# 2_waffling60-MXHS_matrix.net
KiCad netlist of a schematic drawn in Altium Designer
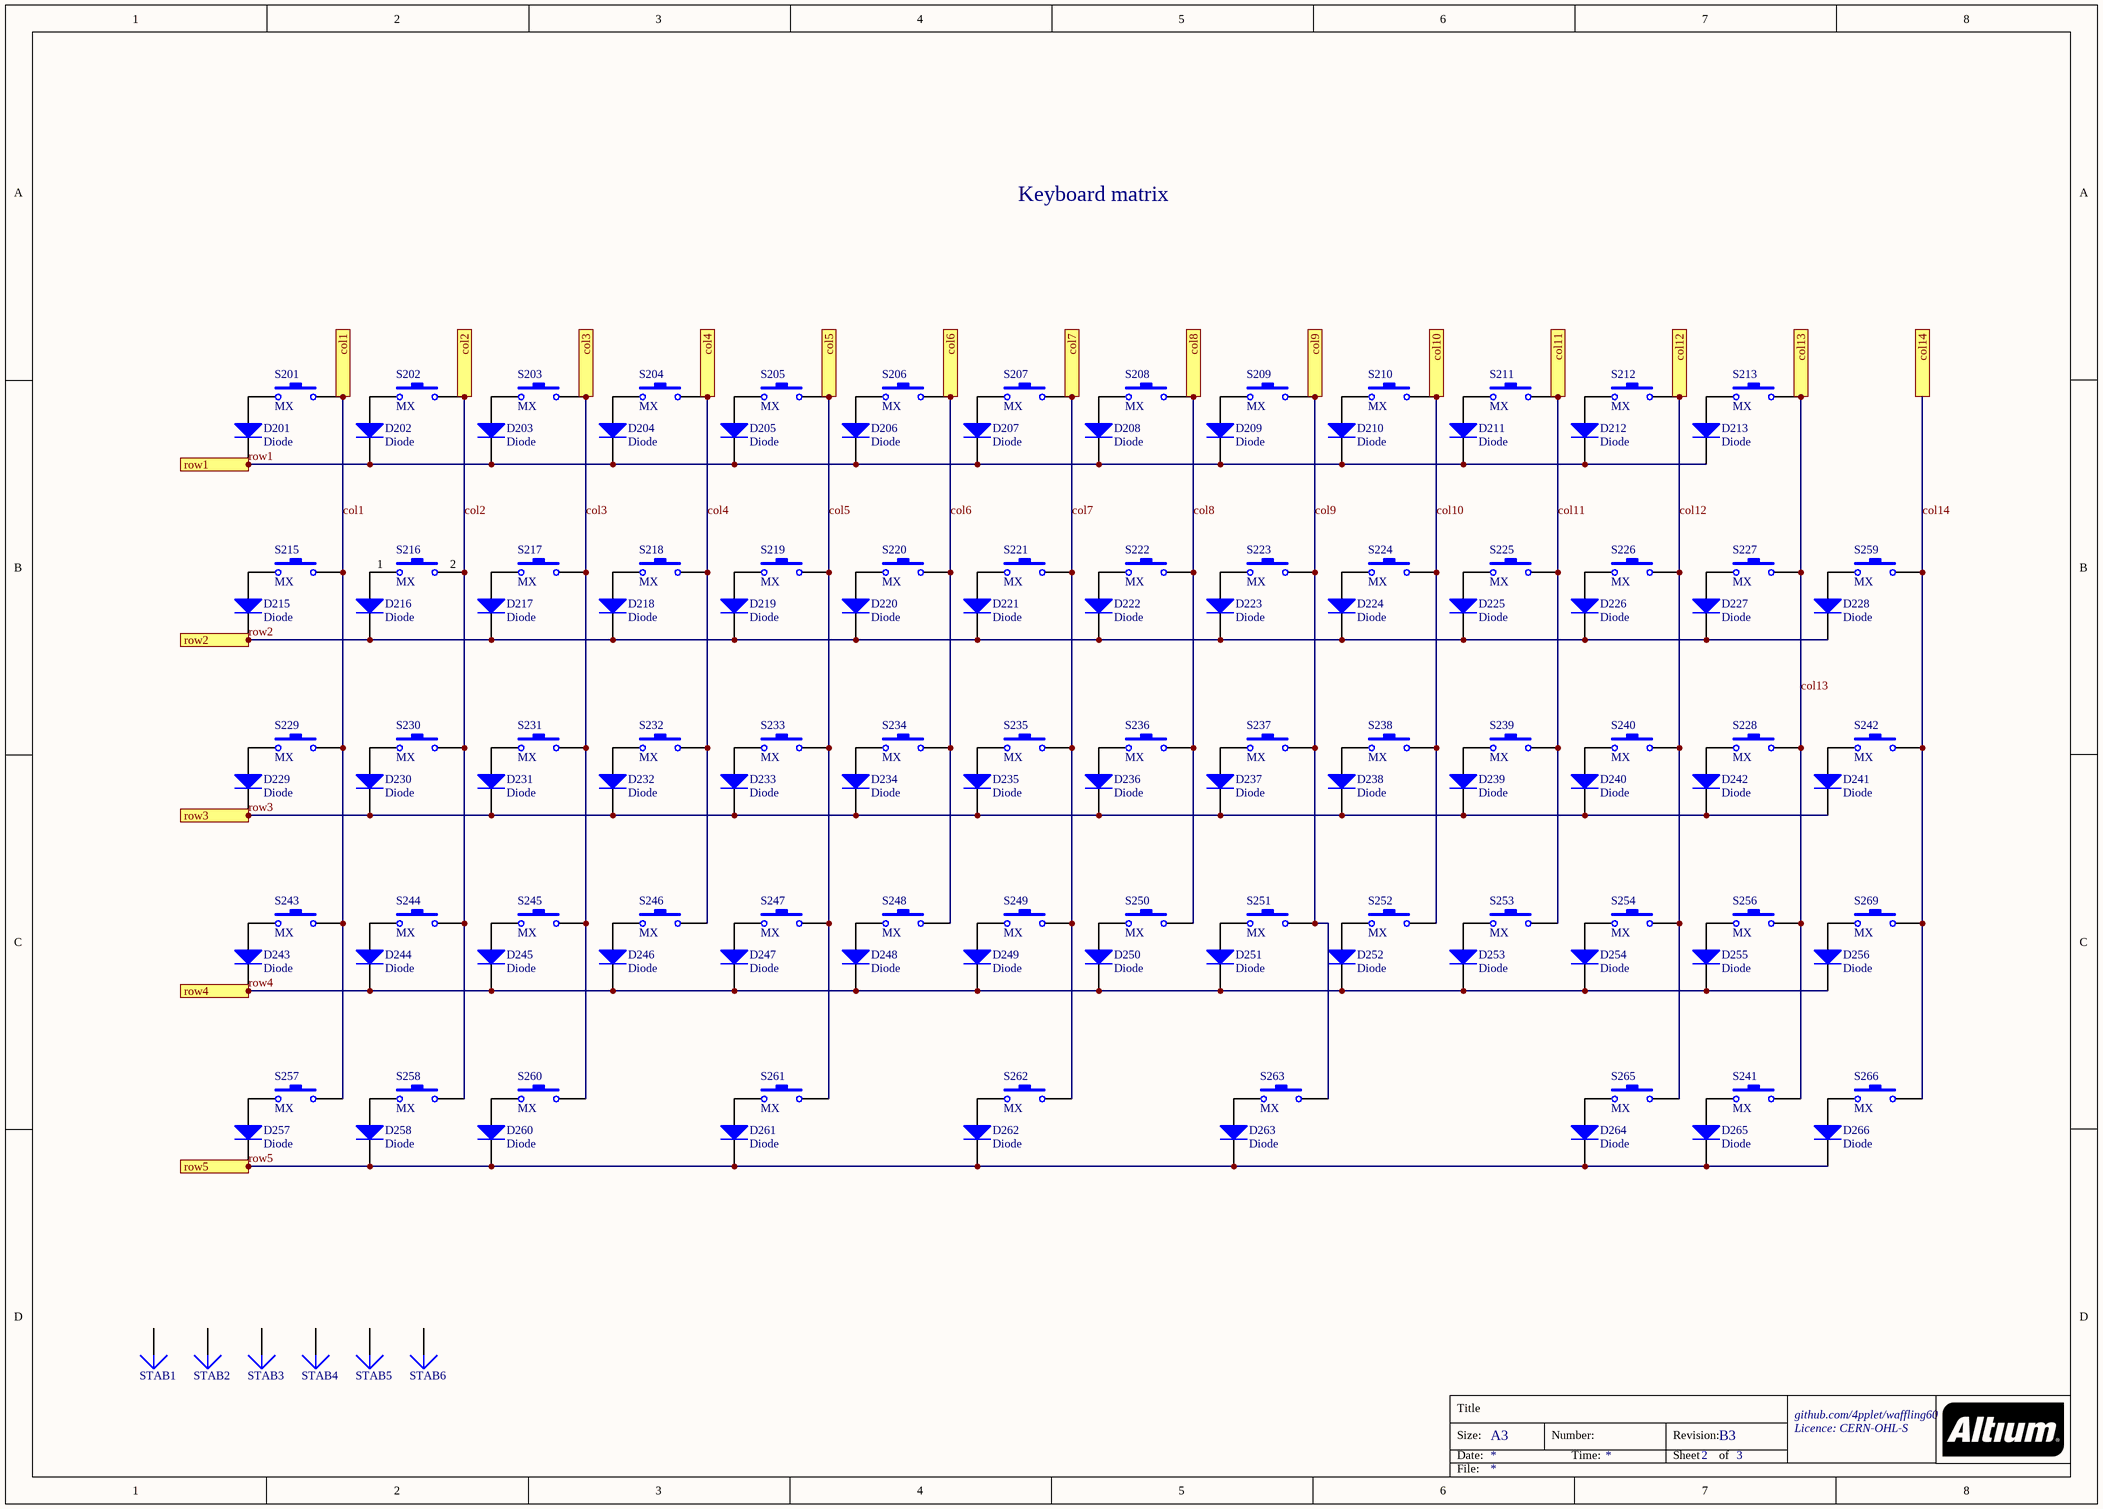
[diagram p0: 2_waffling60-MXHS_matrix.SchDoc]

(export (version "E")
  (design (tool "Eeschema 10.0.6"))
  (components
    (comp (ref "D201")
      (value "Diode")
      (footprint "SOD-123")
      (description "Default Diode")
      (fields (field (name "LCSC PART #") "C81598") (field (name "MRF.PART") "1N4148W"))
      (libsource (lib "Miscellaneous Devices") (part "Diode"))
    )
    (comp (ref "D202")
      (value "Diode")
      (footprint "SOD-123")
      (description "Default Diode")
      (fields (field (name "LCSC PART #") "C81598") (field (name "MRF.PART") "1N4148W"))
      (libsource (lib "Miscellaneous Devices") (part "Diode"))
    )
    (comp (ref "D203")
      (value "Diode")
      (footprint "SOD-123")
      (description "Default Diode")
      (fields (field (name "LCSC PART #") "C81598") (field (name "MRF.PART") "1N4148W"))
      (libsource (lib "Miscellaneous Devices") (part "Diode"))
    )
    (comp (ref "D204")
      (value "Diode")
      (footprint "SOD-123")
      (description "Default Diode")
      (fields (field (name "LCSC PART #") "C81598") (field (name "MRF.PART") "1N4148W"))
      (libsource (lib "Miscellaneous Devices") (part "Diode"))
    )
    (comp (ref "D205")
      (value "Diode")
      (footprint "SOD-123")
      (description "Default Diode")
      (fields (field (name "LCSC PART #") "C81598") (field (name "MRF.PART") "1N4148W"))
      (libsource (lib "Miscellaneous Devices") (part "Diode"))
    )
    (comp (ref "D206")
      (value "Diode")
      (footprint "SOD-123")
      (description "Default Diode")
      (fields (field (name "LCSC PART #") "C81598") (field (name "MRF.PART") "1N4148W"))
      (libsource (lib "Miscellaneous Devices") (part "Diode"))
    )
    (comp (ref "D207")
      (value "Diode")
      (footprint "SOD-123")
      (description "Default Diode")
      (fields (field (name "LCSC PART #") "C81598") (field (name "MRF.PART") "1N4148W"))
      (libsource (lib "Miscellaneous Devices") (part "Diode"))
    )
    (comp (ref "D208")
      (value "Diode")
      (footprint "SOD-123")
      (description "Default Diode")
      (fields (field (name "LCSC PART #") "C81598") (field (name "MRF.PART") "1N4148W"))
      (libsource (lib "Miscellaneous Devices") (part "Diode"))
    )
    (comp (ref "D209")
      (value "Diode")
      (footprint "SOD-123")
      (description "Default Diode")
      (fields (field (name "LCSC PART #") "C81598") (field (name "MRF.PART") "1N4148W"))
      (libsource (lib "Miscellaneous Devices") (part "Diode"))
    )
    (comp (ref "D210")
      (value "Diode")
      (footprint "SOD-123")
      (description "Default Diode")
      (fields (field (name "LCSC PART #") "C81598") (field (name "MRF.PART") "1N4148W"))
      (libsource (lib "Miscellaneous Devices") (part "Diode"))
    )
    (comp (ref "D211")
      (value "Diode")
      (footprint "SOD-123")
      (description "Default Diode")
      (fields (field (name "LCSC PART #") "C81598") (field (name "MRF.PART") "1N4148W"))
      (libsource (lib "Miscellaneous Devices") (part "Diode"))
    )
    (comp (ref "D212")
      (value "Diode")
      (footprint "SOD-123")
      (description "Default Diode")
      (fields (field (name "LCSC PART #") "C81598") (field (name "MRF.PART") "1N4148W"))
      (libsource (lib "Miscellaneous Devices") (part "Diode"))
    )
    (comp (ref "D213")
      (value "Diode")
      (footprint "SOD-123")
      (description "Default Diode")
      (fields (field (name "LCSC PART #") "C81598") (field (name "MRF.PART") "1N4148W"))
      (libsource (lib "Miscellaneous Devices") (part "Diode"))
    )
    (comp (ref "D215")
      (value "Diode")
      (footprint "SOD-123")
      (description "Default Diode")
      (fields (field (name "LCSC PART #") "C81598") (field (name "MRF.PART") "1N4148W"))
      (libsource (lib "Miscellaneous Devices") (part "Diode"))
    )
    (comp (ref "D216")
      (value "Diode")
      (footprint "SOD-123")
      (description "Default Diode")
      (fields (field (name "LCSC PART #") "C81598") (field (name "MRF.PART") "1N4148W"))
      (libsource (lib "Miscellaneous Devices") (part "Diode"))
    )
    (comp (ref "D217")
      (value "Diode")
      (footprint "SOD-123")
      (description "Default Diode")
      (fields (field (name "LCSC PART #") "C81598") (field (name "MRF.PART") "1N4148W"))
      (libsource (lib "Miscellaneous Devices") (part "Diode"))
    )
    (comp (ref "D218")
      (value "Diode")
      (footprint "SOD-123")
      (description "Default Diode")
      (fields (field (name "LCSC PART #") "C81598") (field (name "MRF.PART") "1N4148W"))
      (libsource (lib "Miscellaneous Devices") (part "Diode"))
    )
    (comp (ref "D219")
      (value "Diode")
      (footprint "SOD-123")
      (description "Default Diode")
      (fields (field (name "LCSC PART #") "C81598") (field (name "MRF.PART") "1N4148W"))
      (libsource (lib "Miscellaneous Devices") (part "Diode"))
    )
    (comp (ref "D220")
      (value "Diode")
      (footprint "SOD-123")
      (description "Default Diode")
      (fields (field (name "LCSC PART #") "C81598") (field (name "MRF.PART") "1N4148W"))
      (libsource (lib "Miscellaneous Devices") (part "Diode"))
    )
    (comp (ref "D221")
      (value "Diode")
      (footprint "SOD-123")
      (description "Default Diode")
      (fields (field (name "LCSC PART #") "C81598") (field (name "MRF.PART") "1N4148W"))
      (libsource (lib "Miscellaneous Devices") (part "Diode"))
    )
    (comp (ref "D222")
      (value "Diode")
      (footprint "SOD-123")
      (description "Default Diode")
      (fields (field (name "LCSC PART #") "C81598") (field (name "MRF.PART") "1N4148W"))
      (libsource (lib "Miscellaneous Devices") (part "Diode"))
    )
    (comp (ref "D223")
      (value "Diode")
      (footprint "SOD-123")
      (description "Default Diode")
      (fields (field (name "LCSC PART #") "C81598") (field (name "MRF.PART") "1N4148W"))
      (libsource (lib "Miscellaneous Devices") (part "Diode"))
    )
    (comp (ref "D224")
      (value "Diode")
      (footprint "SOD-123")
      (description "Default Diode")
      (fields (field (name "LCSC PART #") "C81598") (field (name "MRF.PART") "1N4148W"))
      (libsource (lib "Miscellaneous Devices") (part "Diode"))
    )
    (comp (ref "D225")
      (value "Diode")
      (footprint "SOD-123")
      (description "Default Diode")
      (fields (field (name "LCSC PART #") "C81598") (field (name "MRF.PART") "1N4148W"))
      (libsource (lib "Miscellaneous Devices") (part "Diode"))
    )
    (comp (ref "D226")
      (value "Diode")
      (footprint "SOD-123")
      (description "Default Diode")
      (fields (field (name "LCSC PART #") "C81598") (field (name "MRF.PART") "1N4148W"))
      (libsource (lib "Miscellaneous Devices") (part "Diode"))
    )
    (comp (ref "D227")
      (value "Diode")
      (footprint "SOD-123")
      (description "Default Diode")
      (fields (field (name "LCSC PART #") "C81598") (field (name "MRF.PART") "1N4148W"))
      (libsource (lib "Miscellaneous Devices") (part "Diode"))
    )
    (comp (ref "D228")
      (value "Diode")
      (footprint "SOD-123")
      (description "Default Diode")
      (fields (field (name "LCSC PART #") "C81598") (field (name "MRF.PART") "1N4148W"))
      (libsource (lib "Miscellaneous Devices") (part "Diode"))
    )
    (comp (ref "D229")
      (value "Diode")
      (footprint "SOD-123")
      (description "Default Diode")
      (fields (field (name "LCSC PART #") "C81598") (field (name "MRF.PART") "1N4148W"))
      (libsource (lib "Miscellaneous Devices") (part "Diode"))
    )
    (comp (ref "D230")
      (value "Diode")
      (footprint "SOD-123")
      (description "Default Diode")
      (fields (field (name "LCSC PART #") "C81598") (field (name "MRF.PART") "1N4148W"))
      (libsource (lib "Miscellaneous Devices") (part "Diode"))
    )
    (comp (ref "D231")
      (value "Diode")
      (footprint "SOD-123")
      (description "Default Diode")
      (fields (field (name "LCSC PART #") "C81598") (field (name "MRF.PART") "1N4148W"))
      (libsource (lib "Miscellaneous Devices") (part "Diode"))
    )
    (comp (ref "D232")
      (value "Diode")
      (footprint "SOD-123")
      (description "Default Diode")
      (fields (field (name "LCSC PART #") "C81598") (field (name "MRF.PART") "1N4148W"))
      (libsource (lib "Miscellaneous Devices") (part "Diode"))
    )
    (comp (ref "D233")
      (value "Diode")
      (footprint "SOD-123")
      (description "Default Diode")
      (fields (field (name "LCSC PART #") "C81598") (field (name "MRF.PART") "1N4148W"))
      (libsource (lib "Miscellaneous Devices") (part "Diode"))
    )
    (comp (ref "D234")
      (value "Diode")
      (footprint "SOD-123")
      (description "Default Diode")
      (fields (field (name "LCSC PART #") "C81598") (field (name "MRF.PART") "1N4148W"))
      (libsource (lib "Miscellaneous Devices") (part "Diode"))
    )
    (comp (ref "D235")
      (value "Diode")
      (footprint "SOD-123")
      (description "Default Diode")
      (fields (field (name "LCSC PART #") "C81598") (field (name "MRF.PART") "1N4148W"))
      (libsource (lib "Miscellaneous Devices") (part "Diode"))
    )
    (comp (ref "D236")
      (value "Diode")
      (footprint "SOD-123")
      (description "Default Diode")
      (fields (field (name "LCSC PART #") "C81598") (field (name "MRF.PART") "1N4148W"))
      (libsource (lib "Miscellaneous Devices") (part "Diode"))
    )
    (comp (ref "D237")
      (value "Diode")
      (footprint "SOD-123")
      (description "Default Diode")
      (fields (field (name "LCSC PART #") "C81598") (field (name "MRF.PART") "1N4148W"))
      (libsource (lib "Miscellaneous Devices") (part "Diode"))
    )
    (comp (ref "D238")
      (value "Diode")
      (footprint "SOD-123")
      (description "Default Diode")
      (fields (field (name "LCSC PART #") "C81598") (field (name "MRF.PART") "1N4148W"))
      (libsource (lib "Miscellaneous Devices") (part "Diode"))
    )
    (comp (ref "D239")
      (value "Diode")
      (footprint "SOD-123")
      (description "Default Diode")
      (fields (field (name "LCSC PART #") "C81598") (field (name "MRF.PART") "1N4148W"))
      (libsource (lib "Miscellaneous Devices") (part "Diode"))
    )
    (comp (ref "D240")
      (value "Diode")
      (footprint "SOD-123")
      (description "Default Diode")
      (fields (field (name "LCSC PART #") "C81598") (field (name "MRF.PART") "1N4148W"))
      (libsource (lib "Miscellaneous Devices") (part "Diode"))
    )
    (comp (ref "D241")
      (value "Diode")
      (footprint "SOD-123")
      (description "Default Diode")
      (fields (field (name "LCSC PART #") "C81598") (field (name "MRF.PART") "1N4148W"))
      (libsource (lib "Miscellaneous Devices") (part "Diode"))
    )
    (comp (ref "D242")
      (value "Diode")
      (footprint "SOD-123")
      (description "Default Diode")
      (fields (field (name "LCSC PART #") "C81598") (field (name "MRF.PART") "1N4148W"))
      (libsource (lib "Miscellaneous Devices") (part "Diode"))
    )
    (comp (ref "D243")
      (value "Diode")
      (footprint "SOD-123")
      (description "Default Diode")
      (fields (field (name "LCSC PART #") "C81598") (field (name "MRF.PART") "1N4148W"))
      (libsource (lib "Miscellaneous Devices") (part "Diode"))
    )
    (comp (ref "D244")
      (value "Diode")
      (footprint "SOD-123")
      (description "Default Diode")
      (fields (field (name "LCSC PART #") "C81598") (field (name "MRF.PART") "1N4148W"))
      (libsource (lib "Miscellaneous Devices") (part "Diode"))
    )
    (comp (ref "D245")
      (value "Diode")
      (footprint "SOD-123")
      (description "Default Diode")
      (fields (field (name "LCSC PART #") "C81598") (field (name "MRF.PART") "1N4148W"))
      (libsource (lib "Miscellaneous Devices") (part "Diode"))
    )
    (comp (ref "D246")
      (value "Diode")
      (footprint "SOD-123")
      (description "Default Diode")
      (fields (field (name "LCSC PART #") "C81598") (field (name "MRF.PART") "1N4148W"))
      (libsource (lib "Miscellaneous Devices") (part "Diode"))
    )
    (comp (ref "D247")
      (value "Diode")
      (footprint "SOD-123")
      (description "Default Diode")
      (fields (field (name "LCSC PART #") "C81598") (field (name "MRF.PART") "1N4148W"))
      (libsource (lib "Miscellaneous Devices") (part "Diode"))
    )
    (comp (ref "D248")
      (value "Diode")
      (footprint "SOD-123")
      (description "Default Diode")
      (fields (field (name "LCSC PART #") "C81598") (field (name "MRF.PART") "1N4148W"))
      (libsource (lib "Miscellaneous Devices") (part "Diode"))
    )
    (comp (ref "D249")
      (value "Diode")
      (footprint "SOD-123")
      (description "Default Diode")
      (fields (field (name "LCSC PART #") "C81598") (field (name "MRF.PART") "1N4148W"))
      (libsource (lib "Miscellaneous Devices") (part "Diode"))
    )
    (comp (ref "D250")
      (value "Diode")
      (footprint "SOD-123")
      (description "Default Diode")
      (fields (field (name "LCSC PART #") "C81598") (field (name "MRF.PART") "1N4148W"))
      (libsource (lib "Miscellaneous Devices") (part "Diode"))
    )
    (comp (ref "D251")
      (value "Diode")
      (footprint "SOD-123")
      (description "Default Diode")
      (fields (field (name "LCSC PART #") "C81598") (field (name "MRF.PART") "1N4148W"))
      (libsource (lib "Miscellaneous Devices") (part "Diode"))
    )
    (comp (ref "D252")
      (value "Diode")
      (footprint "SOD-123")
      (description "Default Diode")
      (fields (field (name "LCSC PART #") "C81598") (field (name "MRF.PART") "1N4148W"))
      (libsource (lib "Miscellaneous Devices") (part "Diode"))
    )
    (comp (ref "D253")
      (value "Diode")
      (footprint "SOD-123")
      (description "Default Diode")
      (fields (field (name "LCSC PART #") "C81598") (field (name "MRF.PART") "1N4148W"))
      (libsource (lib "Miscellaneous Devices") (part "Diode"))
    )
    (comp (ref "D254")
      (value "Diode")
      (footprint "SOD-123")
      (description "Default Diode")
      (fields (field (name "LCSC PART #") "C81598") (field (name "MRF.PART") "1N4148W"))
      (libsource (lib "Miscellaneous Devices") (part "Diode"))
    )
    (comp (ref "D255")
      (value "Diode")
      (footprint "SOD-123")
      (description "Default Diode")
      (fields (field (name "LCSC PART #") "C81598") (field (name "MRF.PART") "1N4148W"))
      (libsource (lib "Miscellaneous Devices") (part "Diode"))
    )
    (comp (ref "D256")
      (value "Diode")
      (footprint "SOD-123")
      (description "Default Diode")
      (fields (field (name "LCSC PART #") "C81598") (field (name "MRF.PART") "1N4148W"))
      (libsource (lib "Miscellaneous Devices") (part "Diode"))
    )
    (comp (ref "D257")
      (value "Diode")
      (footprint "SOD-123")
      (description "Default Diode")
      (fields (field (name "LCSC PART #") "C81598") (field (name "MRF.PART") "1N4148W"))
      (libsource (lib "Miscellaneous Devices") (part "Diode"))
    )
    (comp (ref "D258")
      (value "Diode")
      (footprint "SOD-123")
      (description "Default Diode")
      (fields (field (name "LCSC PART #") "C81598") (field (name "MRF.PART") "1N4148W"))
      (libsource (lib "Miscellaneous Devices") (part "Diode"))
    )
    (comp (ref "D260")
      (value "Diode")
      (footprint "SOD-123")
      (description "Default Diode")
      (fields (field (name "LCSC PART #") "C81598") (field (name "MRF.PART") "1N4148W"))
      (libsource (lib "Miscellaneous Devices") (part "Diode"))
    )
    (comp (ref "D261")
      (value "Diode")
      (footprint "SOD-123")
      (description "Default Diode")
      (fields (field (name "LCSC PART #") "C81598") (field (name "MRF.PART") "1N4148W"))
      (libsource (lib "Miscellaneous Devices") (part "Diode"))
    )
    (comp (ref "D262")
      (value "Diode")
      (footprint "SOD-123")
      (description "Default Diode")
      (fields (field (name "LCSC PART #") "C81598") (field (name "MRF.PART") "1N4148W"))
      (libsource (lib "Miscellaneous Devices") (part "Diode"))
    )
    (comp (ref "D263")
      (value "Diode")
      (footprint "SOD-123")
      (description "Default Diode")
      (fields (field (name "LCSC PART #") "C81598") (field (name "MRF.PART") "1N4148W"))
      (libsource (lib "Miscellaneous Devices") (part "Diode"))
    )
    (comp (ref "D264")
      (value "Diode")
      (footprint "SOD-123")
      (description "Default Diode")
      (fields (field (name "LCSC PART #") "C81598") (field (name "MRF.PART") "1N4148W"))
      (libsource (lib "Miscellaneous Devices") (part "Diode"))
    )
    (comp (ref "D265")
      (value "Diode")
      (footprint "SOD-123")
      (description "Default Diode")
      (fields (field (name "LCSC PART #") "C81598") (field (name "MRF.PART") "1N4148W"))
      (libsource (lib "Miscellaneous Devices") (part "Diode"))
    )
    (comp (ref "D266")
      (value "Diode")
      (footprint "SOD-123")
      (description "Default Diode")
      (fields (field (name "LCSC PART #") "C81598") (field (name "MRF.PART") "1N4148W"))
      (libsource (lib "Miscellaneous Devices") (part "Diode"))
    )
    (comp (ref "S201")
      (value "MX")
      (footprint "MXHS-switch - 1U Top layer")
      (description "Switch")
      (fields (field (name "MFG") "Kailh"))
      (libsource (lib "Miscellaneous Devices") (part "SW-PB"))
    )
    (comp (ref "S202")
      (value "MX")
      (footprint "MXHS-switch - 1U Top layer - switched pol")
      (description "Switch")
      (fields (field (name "MFG") "Kailh"))
      (libsource (lib "Miscellaneous Devices") (part "SW-PB"))
    )
    (comp (ref "S203")
      (value "MX")
      (footprint "MXHS-switch - 1U Top layer")
      (description "Switch")
      (fields (field (name "MFG") "Kailh"))
      (libsource (lib "Miscellaneous Devices") (part "SW-PB"))
    )
    (comp (ref "S204")
      (value "MX")
      (footprint "MXHS-switch - 1U Top layer - switched pol")
      (description "Switch")
      (fields (field (name "MFG") "Kailh"))
      (libsource (lib "Miscellaneous Devices") (part "SW-PB"))
    )
    (comp (ref "S205")
      (value "MX")
      (footprint "MXHS-switch - 1U Top layer")
      (description "Switch")
      (fields (field (name "MFG") "Kailh"))
      (libsource (lib "Miscellaneous Devices") (part "SW-PB"))
    )
    (comp (ref "S206")
      (value "MX")
      (footprint "MXHS-switch - 1U Top layer")
      (description "Switch")
      (fields (field (name "MFG") "Kailh"))
      (libsource (lib "Miscellaneous Devices") (part "SW-PB"))
    )
    (comp (ref "S207")
      (value "MX")
      (footprint "MXHS-switch - 1U Top layer")
      (description "Switch")
      (fields (field (name "MFG") "Kailh"))
      (libsource (lib "Miscellaneous Devices") (part "SW-PB"))
    )
    (comp (ref "S208")
      (value "MX")
      (footprint "MXHS-switch - 1U Top layer")
      (description "Switch")
      (fields (field (name "MFG") "Kailh"))
      (libsource (lib "Miscellaneous Devices") (part "SW-PB"))
    )
    (comp (ref "S209")
      (value "MX")
      (footprint "MXHS-switch - 1U Top layer")
      (description "Switch")
      (fields (field (name "MFG") "Kailh"))
      (libsource (lib "Miscellaneous Devices") (part "SW-PB"))
    )
    (comp (ref "S210")
      (value "MX")
      (footprint "MXHS-switch - 1U Top layer")
      (description "Switch")
      (fields (field (name "MFG") "Kailh"))
      (libsource (lib "Miscellaneous Devices") (part "SW-PB"))
    )
    (comp (ref "S211")
      (value "MX")
      (footprint "MXHS-switch - 1U Top layer - switched pol")
      (description "Switch")
      (fields (field (name "MFG") "Kailh"))
      (libsource (lib "Miscellaneous Devices") (part "SW-PB"))
    )
    (comp (ref "S212")
      (value "MX")
      (footprint "MXHS-switch - 1U Top layer")
      (description "Switch")
      (fields (field (name "MFG") "Kailh"))
      (libsource (lib "Miscellaneous Devices") (part "SW-PB"))
    )
    (comp (ref "S213")
      (value "MX")
      (footprint "MXHS-switch - 1U Top layer")
      (description "Switch")
      (fields (field (name "MFG") "Kailh"))
      (libsource (lib "Miscellaneous Devices") (part "SW-PB"))
    )
    (comp (ref "S215")
      (value "MX")
      (footprint "MXHS-switch - 1U Top layer")
      (description "TAB")
      (fields (field (name "MFG") "Kailh"))
      (libsource (lib "Miscellaneous Devices") (part "SW-PB"))
    )
    (comp (ref "S216")
      (value "MX")
      (footprint "MXHS-switch - 1U Top layer - switched pol")
      (description "Switch")
      (fields (field (name "MFG") "Kailh"))
      (libsource (lib "") (part "SW-PB_1"))
    )
    (comp (ref "S217")
      (value "MX")
      (footprint "MXHS-switch - 1U Top layer")
      (description "Switch")
      (fields (field (name "MFG") "Kailh"))
      (libsource (lib "Miscellaneous Devices") (part "SW-PB"))
    )
    (comp (ref "S218")
      (value "MX")
      (footprint "MXHS-switch - 1U Top layer")
      (description "Switch")
      (fields (field (name "MFG") "Kailh"))
      (libsource (lib "Miscellaneous Devices") (part "SW-PB"))
    )
    (comp (ref "S219")
      (value "MX")
      (footprint "MXHS-switch - 1U Top layer")
      (description "Switch")
      (fields (field (name "MFG") "Kailh"))
      (libsource (lib "Miscellaneous Devices") (part "SW-PB"))
    )
    (comp (ref "S220")
      (value "MX")
      (footprint "MXHS-switch - 1U Top layer - switched pol")
      (description "Switch")
      (fields (field (name "MFG") "Kailh"))
      (libsource (lib "Miscellaneous Devices") (part "SW-PB"))
    )
    (comp (ref "S221")
      (value "MX")
      (footprint "MXHS-switch - 1U Top layer")
      (description "Switch")
      (fields (field (name "MFG") "Kailh"))
      (libsource (lib "Miscellaneous Devices") (part "SW-PB"))
    )
    (comp (ref "S222")
      (value "MX")
      (footprint "MXHS-switch - 1U Top layer - switched pol")
      (description "Switch")
      (fields (field (name "MFG") "Kailh"))
      (libsource (lib "Miscellaneous Devices") (part "SW-PB"))
    )
    (comp (ref "S223")
      (value "MX")
      (footprint "MXHS-switch - 1U Top layer")
      (description "Switch")
      (fields (field (name "MFG") "Kailh"))
      (libsource (lib "Miscellaneous Devices") (part "SW-PB"))
    )
    (comp (ref "S224")
      (value "MX")
      (footprint "MXHS-switch - 1U Top layer")
      (description "Switch")
      (fields (field (name "MFG") "Kailh"))
      (libsource (lib "Miscellaneous Devices") (part "SW-PB"))
    )
    (comp (ref "S225")
      (value "MX")
      (footprint "MXHS-switch - 1U Top layer")
      (description "Switch")
      (fields (field (name "MFG") "Kailh"))
      (libsource (lib "Miscellaneous Devices") (part "SW-PB"))
    )
    (comp (ref "S226")
      (value "MX")
      (footprint "MXHS-switch - 1U Top layer")
      (description "Switch")
      (fields (field (name "MFG") "Kailh"))
      (libsource (lib "Miscellaneous Devices") (part "SW-PB"))
    )
    (comp (ref "S227")
      (value "MX")
      (footprint "MXHS-switch - 1U Top layer - switched pol")
      (description "Switch")
      (fields (field (name "MFG") "Kailh"))
      (libsource (lib "Miscellaneous Devices") (part "SW-PB"))
    )
    (comp (ref "S228")
      (value "MX")
      (footprint "MXHS-switch - 1U Top layer - switched pol")
      (description "Switch")
      (fields (field (name "MFG") "Kailh"))
      (libsource (lib "Miscellaneous Devices") (part "SW-PB"))
    )
    (comp (ref "S229")
      (value "MX")
      (footprint "MXHS-switch - 1U Top layer")
      (description "Switch")
      (fields (field (name "MFG") "Kailh"))
      (libsource (lib "Miscellaneous Devices") (part "SW-PB"))
    )
    (comp (ref "S230")
      (value "MX")
      (footprint "MXHS-switch - 1U Top layer - switched pol")
      (description "Switch")
      (fields (field (name "MFG") "Kailh"))
      (libsource (lib "Miscellaneous Devices") (part "SW-PB"))
    )
    (comp (ref "S231")
      (value "MX")
      (footprint "MXHS-switch - 1U Top layer")
      (description "Switch")
      (fields (field (name "MFG") "Kailh"))
      (libsource (lib "Miscellaneous Devices") (part "SW-PB"))
    )
    (comp (ref "S232")
      (value "MX")
      (footprint "MXHS-switch - 1U Top layer")
      (description "Switch")
      (fields (field (name "MFG") "Kailh"))
      (libsource (lib "Miscellaneous Devices") (part "SW-PB"))
    )
    (comp (ref "S233")
      (value "MX")
      (footprint "MXHS-switch - 1U Top layer")
      (description "Switch")
      (fields (field (name "MFG") "Kailh"))
      (libsource (lib "Miscellaneous Devices") (part "SW-PB"))
    )
    (comp (ref "S234")
      (value "MX")
      (footprint "MXHS-switch - 1U Top layer - switched pol")
      (description "Switch")
      (fields (field (name "MFG") "Kailh"))
      (libsource (lib "Miscellaneous Devices") (part "SW-PB"))
    )
    (comp (ref "S235")
      (value "MX")
      (footprint "MXHS-switch - 1U Top layer")
      (description "Switch")
      (fields (field (name "MFG") "Kailh"))
      (libsource (lib "Miscellaneous Devices") (part "SW-PB"))
    )
    (comp (ref "S236")
      (value "MX")
      (footprint "MXHS-switch - 1U Top layer")
      (description "Switch")
      (fields (field (name "MFG") "Kailh"))
      (libsource (lib "Miscellaneous Devices") (part "SW-PB"))
    )
    (comp (ref "S237")
      (value "MX")
      (footprint "MXHS-switch - 1U Top layer")
      (description "Switch")
      (fields (field (name "MFG") "Kailh"))
      (libsource (lib "Miscellaneous Devices") (part "SW-PB"))
    )
    (comp (ref "S238")
      (value "MX")
      (footprint "MXHS-switch - 1U Top layer")
      (description "Switch")
      (fields (field (name "MFG") "Kailh"))
      (libsource (lib "Miscellaneous Devices") (part "SW-PB"))
    )
    (comp (ref "S239")
      (value "MX")
      (footprint "MXHS-switch - 1U Top layer")
      (description "Switch")
      (fields (field (name "MFG") "Kailh"))
      (libsource (lib "Miscellaneous Devices") (part "SW-PB"))
    )
    (comp (ref "S240")
      (value "MX")
      (footprint "MXHS-switch - 1U Top layer")
      (description "Switch")
      (fields (field (name "MFG") "Kailh"))
      (libsource (lib "Miscellaneous Devices") (part "SW-PB"))
    )
    (comp (ref "S241")
      (value "MX")
      (footprint "MXHS-switch - 1U Top layer")
      (description "Switch")
      (fields (field (name "MFG") "Kailh"))
      (libsource (lib "Miscellaneous Devices") (part "SW-PB"))
    )
    (comp (ref "S242")
      (value "MX")
      (footprint "MXHS-switch - 1U Top layer - switched pol")
      (description "Switch")
      (fields (field (name "MFG") "Kailh"))
      (libsource (lib "Miscellaneous Devices") (part "SW-PB"))
    )
    (comp (ref "S243")
      (value "MX")
      (footprint "MXHS-switch - 1U Top layer")
      (description "Switch")
      (fields (field (name "MFG") "Kailh"))
      (libsource (lib "Miscellaneous Devices") (part "SW-PB"))
    )
    (comp (ref "S244")
      (value "MX")
      (footprint "MXHS-switch - 1U Top layer - switched pol")
      (description "Switch")
      (fields (field (name "MFG") "Kailh"))
      (libsource (lib "Miscellaneous Devices") (part "SW-PB"))
    )
    (comp (ref "S245")
      (value "MX")
      (footprint "MXHS-switch - 1U Top layer")
      (description "Switch")
      (fields (field (name "MFG") "Kailh"))
      (libsource (lib "Miscellaneous Devices") (part "SW-PB"))
    )
    (comp (ref "S246")
      (value "MX")
      (footprint "MXHS-switch - 1U Top layer")
      (description "Switch")
      (fields (field (name "MFG") "Kailh"))
      (libsource (lib "Miscellaneous Devices") (part "SW-PB"))
    )
    (comp (ref "S247")
      (value "MX")
      (footprint "MXHS-switch - 1U Top layer")
      (description "Switch")
      (fields (field (name "MFG") "Kailh"))
      (libsource (lib "Miscellaneous Devices") (part "SW-PB"))
    )
    (comp (ref "S248")
      (value "MX")
      (footprint "MXHS-switch - 1U Top layer")
      (description "Switch")
      (fields (field (name "MFG") "Kailh"))
      (libsource (lib "Miscellaneous Devices") (part "SW-PB"))
    )
    (comp (ref "S249")
      (value "MX")
      (footprint "MXHS-switch - 1U Top layer")
      (description "Switch")
      (fields (field (name "MFG") "Kailh"))
      (libsource (lib "Miscellaneous Devices") (part "SW-PB"))
    )
    (comp (ref "S250")
      (value "MX")
      (footprint "MXHS-switch - 1U Top layer")
      (description "Switch")
      (fields (field (name "MFG") "Kailh"))
      (libsource (lib "Miscellaneous Devices") (part "SW-PB"))
    )
    (comp (ref "S251")
      (value "MX")
      (footprint "MXHS-switch - 1U Top layer")
      (description "Switch")
      (fields (field (name "MFG") "Kailh"))
      (libsource (lib "Miscellaneous Devices") (part "SW-PB"))
    )
    (comp (ref "S252")
      (value "MX")
      (footprint "MXHS-switch - 1U Top layer")
      (description "Switch")
      (fields (field (name "MFG") "Kailh"))
      (libsource (lib "Miscellaneous Devices") (part "SW-PB"))
    )
    (comp (ref "S253")
      (value "MX")
      (footprint "MXHS-switch - 1U Top layer")
      (description "Switch")
      (fields (field (name "MFG") "Kailh"))
      (libsource (lib "Miscellaneous Devices") (part "SW-PB"))
    )
    (comp (ref "S254")
      (value "MX")
      (footprint "MXHS-switch - 1U Top layer")
      (description "Switch")
      (fields (field (name "MFG") "Kailh"))
      (libsource (lib "Miscellaneous Devices") (part "SW-PB"))
    )
    (comp (ref "S256")
      (value "MX")
      (footprint "MXHS-switch - 1U Top layer")
      (description "Switch")
      (fields (field (name "MFG") "Kailh"))
      (libsource (lib "Miscellaneous Devices") (part "SW-PB"))
    )
    (comp (ref "S257")
      (value "MX")
      (footprint "MXHS-switch - 1U Top layer - switched pol")
      (description "Switch")
      (fields (field (name "MFG") "Kailh"))
      (libsource (lib "Miscellaneous Devices") (part "SW-PB"))
    )
    (comp (ref "S258")
      (value "MX")
      (footprint "MXHS-switch - 1U Top layer")
      (description "Switch")
      (fields (field (name "MFG") "Kailh"))
      (libsource (lib "Miscellaneous Devices") (part "SW-PB"))
    )
    (comp (ref "S259")
      (value "MX")
      (footprint "MXHS-switch - 1U Top layer - switched pol")
      (description "Switch")
      (fields (field (name "MFG") "Kailh"))
      (libsource (lib "Miscellaneous Devices") (part "SW-PB"))
    )
    (comp (ref "S260")
      (value "MX")
      (footprint "MXHS-switch - 1U Top layer")
      (description "Switch")
      (fields (field (name "MFG") "Kailh"))
      (libsource (lib "Miscellaneous Devices") (part "SW-PB"))
    )
    (comp (ref "S261")
      (value "MX")
      (footprint "MXHS-switch - 1U Top layer")
      (description "Switch")
      (fields (field (name "MFG") "Kailh"))
      (libsource (lib "Miscellaneous Devices") (part "SW-PB"))
    )
    (comp (ref "S262")
      (value "MX")
      (footprint "MXHS-switch - 1U Top layer - switched pol")
      (description "Switch")
      (fields (field (name "MFG") "Kailh"))
      (libsource (lib "Miscellaneous Devices") (part "SW-PB"))
    )
    (comp (ref "S263")
      (value "MX")
      (footprint "MXHS-switch - 1U Top layer")
      (description "Switch")
      (fields (field (name "MFG") "Kailh"))
      (libsource (lib "Miscellaneous Devices") (part "SW-PB"))
    )
    (comp (ref "S265")
      (value "MX")
      (footprint "MXHS-switch - 1U Top layer - switched pol")
      (description "Switch")
      (fields (field (name "MFG") "Kailh"))
      (libsource (lib "Miscellaneous Devices") (part "SW-PB"))
    )
    (comp (ref "S266")
      (value "MX")
      (footprint "MXHS-switch - 1U Top layer - switched pol")
      (description "Switch")
      (fields (field (name "MFG") "Kailh"))
      (libsource (lib "Miscellaneous Devices") (part "SW-PB"))
    )
    (comp (ref "S269")
      (value "MX")
      (footprint "MXHS-switch - 1U Top layer")
      (description "Switch")
      (fields (field (name "MFG") "Kailh"))
      (libsource (lib "Miscellaneous Devices") (part "SW-PB"))
    )
    (comp (ref "STAB1")
      (value "Plug")
      (footprint "Stab 2u")
      (libsource (lib "Miscellaneous Connectors") (part "Plug"))
    )
    (comp (ref "STAB2")
      (value "Plug")
      (footprint "Stab 2u")
      (libsource (lib "Miscellaneous Connectors") (part "Plug"))
    )
    (comp (ref "STAB3")
      (value "Plug")
      (footprint "Stab 7U")
      (libsource (lib "Miscellaneous Connectors") (part "Plug"))
    )
    (comp (ref "STAB4")
      (value "Plug")
      (footprint "Stab 10U")
      (libsource (lib "Miscellaneous Connectors") (part "Plug"))
    )
    (comp (ref "STAB5")
      (value "Plug")
      (footprint "Stab 3u")
      (libsource (lib "Miscellaneous Connectors") (part "Plug"))
    )
    (comp (ref "STAB6")
      (value "Plug")
      (footprint "Stab 3u")
      (libsource (lib "Miscellaneous Connectors") (part "Plug"))
    )
  )
  (nets
    (net (code "1") (name "/col1") (class "Default")
      (node (ref "S201") (pin "2") (pinfunction "2_2") (pintype "passive"))
      (node (ref "S215") (pin "2") (pinfunction "2_2") (pintype "passive"))
      (node (ref "S229") (pin "2") (pinfunction "2_2") (pintype "passive"))
      (node (ref "S243") (pin "2") (pinfunction "2_2") (pintype "passive"))
      (node (ref "S257") (pin "1") (pinfunction "1_1") (pintype "passive"))
    )
    (net (code "2") (name "/col2") (class "Default")
      (node (ref "S202") (pin "2") (pinfunction "2_2") (pintype "passive"))
      (node (ref "S216") (pin "2") (pinfunction "2_2") (pintype "passive"))
      (node (ref "S230") (pin "2") (pinfunction "2_2") (pintype "passive"))
      (node (ref "S244") (pin "1") (pinfunction "1_1") (pintype "passive"))
      (node (ref "S258") (pin "2") (pinfunction "2_2") (pintype "passive"))
    )
    (net (code "3") (name "/col3") (class "Default")
      (node (ref "S203") (pin "2") (pinfunction "2_2") (pintype "passive"))
      (node (ref "S217") (pin "2") (pinfunction "2_2") (pintype "passive"))
      (node (ref "S231") (pin "2") (pinfunction "2_2") (pintype "passive"))
      (node (ref "S245") (pin "2") (pinfunction "2_2") (pintype "passive"))
      (node (ref "S260") (pin "2") (pinfunction "2_2") (pintype "passive"))
    )
    (net (code "4") (name "/col4") (class "Default")
      (node (ref "S204") (pin "2") (pinfunction "2_2") (pintype "passive"))
      (node (ref "S218") (pin "2") (pinfunction "2_2") (pintype "passive"))
      (node (ref "S232") (pin "2") (pinfunction "2_2") (pintype "passive"))
      (node (ref "S246") (pin "2") (pinfunction "2_2") (pintype "passive"))
    )
    (net (code "5") (name "/col5") (class "Default")
      (node (ref "S205") (pin "2") (pinfunction "2_2") (pintype "passive"))
      (node (ref "S219") (pin "2") (pinfunction "2_2") (pintype "passive"))
      (node (ref "S233") (pin "2") (pinfunction "2_2") (pintype "passive"))
      (node (ref "S247") (pin "2") (pinfunction "2_2") (pintype "passive"))
      (node (ref "S261") (pin "2") (pinfunction "2_2") (pintype "passive"))
    )
    (net (code "6") (name "/col6") (class "Default")
      (node (ref "S206") (pin "2") (pinfunction "2_2") (pintype "passive"))
      (node (ref "S220") (pin "2") (pinfunction "2_2") (pintype "passive"))
      (node (ref "S234") (pin "2") (pinfunction "2_2") (pintype "passive"))
      (node (ref "S248") (pin "2") (pinfunction "2_2") (pintype "passive"))
    )
    (net (code "7") (name "/col7") (class "Default")
      (node (ref "S207") (pin "2") (pinfunction "2_2") (pintype "passive"))
      (node (ref "S221") (pin "2") (pinfunction "2_2") (pintype "passive"))
      (node (ref "S235") (pin "2") (pinfunction "2_2") (pintype "passive"))
      (node (ref "S249") (pin "2") (pinfunction "2_2") (pintype "passive"))
      (node (ref "S262") (pin "1") (pinfunction "1_1") (pintype "passive"))
    )
    (net (code "8") (name "/col8") (class "Default")
      (node (ref "S208") (pin "2") (pinfunction "2_2") (pintype "passive"))
      (node (ref "S222") (pin "2") (pinfunction "2_2") (pintype "passive"))
      (node (ref "S236") (pin "2") (pinfunction "2_2") (pintype "passive"))
      (node (ref "S250") (pin "2") (pinfunction "2_2") (pintype "passive"))
    )
    (net (code "9") (name "/col9") (class "Default")
      (node (ref "S209") (pin "2") (pinfunction "2_2") (pintype "passive"))
      (node (ref "S223") (pin "2") (pinfunction "2_2") (pintype "passive"))
      (node (ref "S237") (pin "2") (pinfunction "2_2") (pintype "passive"))
      (node (ref "S251") (pin "2") (pinfunction "2_2") (pintype "passive"))
      (node (ref "S263") (pin "2") (pinfunction "2_2") (pintype "passive"))
    )
    (net (code "10") (name "/col10") (class "Default")
      (node (ref "S210") (pin "2") (pinfunction "2_2") (pintype "passive"))
      (node (ref "S224") (pin "2") (pinfunction "2_2") (pintype "passive"))
      (node (ref "S238") (pin "2") (pinfunction "2_2") (pintype "passive"))
      (node (ref "S252") (pin "2") (pinfunction "2_2") (pintype "passive"))
    )
    (net (code "11") (name "/col11") (class "Default")
      (node (ref "S211") (pin "2") (pinfunction "2_2") (pintype "passive"))
      (node (ref "S225") (pin "2") (pinfunction "2_2") (pintype "passive"))
      (node (ref "S239") (pin "2") (pinfunction "2_2") (pintype "passive"))
      (node (ref "S253") (pin "2") (pinfunction "2_2") (pintype "passive"))
    )
    (net (code "12") (name "/col12") (class "Default")
      (node (ref "S212") (pin "2") (pinfunction "2_2") (pintype "passive"))
      (node (ref "S226") (pin "2") (pinfunction "2_2") (pintype "passive"))
      (node (ref "S240") (pin "2") (pinfunction "2_2") (pintype "passive"))
      (node (ref "S254") (pin "2") (pinfunction "2_2") (pintype "passive"))
      (node (ref "S265") (pin "2") (pinfunction "2_2") (pintype "passive"))
    )
    (net (code "13") (name "/col13") (class "Default")
      (node (ref "S213") (pin "2") (pinfunction "2_2") (pintype "passive"))
      (node (ref "S227") (pin "2") (pinfunction "2_2") (pintype "passive"))
      (node (ref "S228") (pin "2") (pinfunction "2_2") (pintype "passive"))
      (node (ref "S241") (pin "1") (pinfunction "1_1") (pintype "passive"))
      (node (ref "S256") (pin "2") (pinfunction "2_2") (pintype "passive"))
    )
    (net (code "14") (name "/col14") (class "Default")
      (node (ref "S242") (pin "2") (pinfunction "2_2") (pintype "passive"))
      (node (ref "S259") (pin "2") (pinfunction "2_2") (pintype "passive"))
      (node (ref "S266") (pin "2") (pinfunction "2_2") (pintype "passive"))
      (node (ref "S269") (pin "2") (pinfunction "2_2") (pintype "passive"))
    )
    (net (code "15") (name "/row1") (class "Default")
      (node (ref "D201") (pin "2") (pinfunction "K_2") (pintype "passive"))
      (node (ref "D202") (pin "2") (pinfunction "K_2") (pintype "passive"))
      (node (ref "D203") (pin "2") (pinfunction "K_2") (pintype "passive"))
      (node (ref "D204") (pin "2") (pinfunction "K_2") (pintype "passive"))
      (node (ref "D205") (pin "2") (pinfunction "K_2") (pintype "passive"))
      (node (ref "D206") (pin "2") (pinfunction "K_2") (pintype "passive"))
      (node (ref "D207") (pin "2") (pinfunction "K_2") (pintype "passive"))
      (node (ref "D208") (pin "2") (pinfunction "K_2") (pintype "passive"))
      (node (ref "D209") (pin "2") (pinfunction "K_2") (pintype "passive"))
      (node (ref "D210") (pin "2") (pinfunction "K_2") (pintype "passive"))
      (node (ref "D211") (pin "2") (pinfunction "K_2") (pintype "passive"))
      (node (ref "D212") (pin "2") (pinfunction "K_2") (pintype "passive"))
      (node (ref "D213") (pin "2") (pinfunction "K_2") (pintype "passive"))
    )
    (net (code "16") (name "/row2") (class "Default")
      (node (ref "D215") (pin "2") (pinfunction "K_2") (pintype "passive"))
      (node (ref "D216") (pin "2") (pinfunction "K_2") (pintype "passive"))
      (node (ref "D217") (pin "2") (pinfunction "K_2") (pintype "passive"))
      (node (ref "D218") (pin "2") (pinfunction "K_2") (pintype "passive"))
      (node (ref "D219") (pin "2") (pinfunction "K_2") (pintype "passive"))
      (node (ref "D220") (pin "2") (pinfunction "K_2") (pintype "passive"))
      (node (ref "D221") (pin "2") (pinfunction "K_2") (pintype "passive"))
      (node (ref "D222") (pin "2") (pinfunction "K_2") (pintype "passive"))
      (node (ref "D223") (pin "2") (pinfunction "K_2") (pintype "passive"))
      (node (ref "D224") (pin "2") (pinfunction "K_2") (pintype "passive"))
      (node (ref "D225") (pin "2") (pinfunction "K_2") (pintype "passive"))
      (node (ref "D226") (pin "2") (pinfunction "K_2") (pintype "passive"))
      (node (ref "D227") (pin "2") (pinfunction "K_2") (pintype "passive"))
      (node (ref "D228") (pin "2") (pinfunction "K_2") (pintype "passive"))
    )
    (net (code "17") (name "/row3") (class "Default")
      (node (ref "D229") (pin "2") (pinfunction "K_2") (pintype "passive"))
      (node (ref "D230") (pin "2") (pinfunction "K_2") (pintype "passive"))
      (node (ref "D231") (pin "2") (pinfunction "K_2") (pintype "passive"))
      (node (ref "D232") (pin "2") (pinfunction "K_2") (pintype "passive"))
      (node (ref "D233") (pin "2") (pinfunction "K_2") (pintype "passive"))
      (node (ref "D234") (pin "2") (pinfunction "K_2") (pintype "passive"))
      (node (ref "D235") (pin "2") (pinfunction "K_2") (pintype "passive"))
      (node (ref "D236") (pin "2") (pinfunction "K_2") (pintype "passive"))
      (node (ref "D237") (pin "2") (pinfunction "K_2") (pintype "passive"))
      (node (ref "D238") (pin "2") (pinfunction "K_2") (pintype "passive"))
      (node (ref "D239") (pin "2") (pinfunction "K_2") (pintype "passive"))
      (node (ref "D240") (pin "2") (pinfunction "K_2") (pintype "passive"))
      (node (ref "D241") (pin "2") (pinfunction "K_2") (pintype "passive"))
      (node (ref "D242") (pin "2") (pinfunction "K_2") (pintype "passive"))
    )
    (net (code "18") (name "/row4") (class "Default")
      (node (ref "D243") (pin "2") (pinfunction "K_2") (pintype "passive"))
      (node (ref "D244") (pin "2") (pinfunction "K_2") (pintype "passive"))
      (node (ref "D245") (pin "2") (pinfunction "K_2") (pintype "passive"))
      (node (ref "D246") (pin "2") (pinfunction "K_2") (pintype "passive"))
      (node (ref "D247") (pin "2") (pinfunction "K_2") (pintype "passive"))
      (node (ref "D248") (pin "2") (pinfunction "K_2") (pintype "passive"))
      (node (ref "D249") (pin "2") (pinfunction "K_2") (pintype "passive"))
      (node (ref "D250") (pin "2") (pinfunction "K_2") (pintype "passive"))
      (node (ref "D251") (pin "2") (pinfunction "K_2") (pintype "passive"))
      (node (ref "D252") (pin "2") (pinfunction "K_2") (pintype "passive"))
      (node (ref "D253") (pin "2") (pinfunction "K_2") (pintype "passive"))
      (node (ref "D254") (pin "2") (pinfunction "K_2") (pintype "passive"))
      (node (ref "D255") (pin "2") (pinfunction "K_2") (pintype "passive"))
      (node (ref "D256") (pin "2") (pinfunction "K_2") (pintype "passive"))
    )
    (net (code "19") (name "/row5") (class "Default")
      (node (ref "D257") (pin "2") (pinfunction "K_2") (pintype "passive"))
      (node (ref "D258") (pin "2") (pinfunction "K_2") (pintype "passive"))
      (node (ref "D260") (pin "2") (pinfunction "K_2") (pintype "passive"))
      (node (ref "D261") (pin "2") (pinfunction "K_2") (pintype "passive"))
      (node (ref "D262") (pin "2") (pinfunction "K_2") (pintype "passive"))
      (node (ref "D263") (pin "2") (pinfunction "K_2") (pintype "passive"))
      (node (ref "D264") (pin "2") (pinfunction "K_2") (pintype "passive"))
      (node (ref "D265") (pin "2") (pinfunction "K_2") (pintype "passive"))
      (node (ref "D266") (pin "2") (pinfunction "K_2") (pintype "passive"))
    )
    (net (code "20") (name "Net-(D201-A)") (class "Default")
      (node (ref "D201") (pin "1") (pinfunction "A_1") (pintype "passive"))
      (node (ref "S201") (pin "1") (pinfunction "1_1") (pintype "passive"))
    )
    (net (code "21") (name "Net-(D202-A)") (class "Default")
      (node (ref "D202") (pin "1") (pinfunction "A_1") (pintype "passive"))
      (node (ref "S202") (pin "1") (pinfunction "1_1") (pintype "passive"))
    )
    (net (code "22") (name "Net-(D203-A)") (class "Default")
      (node (ref "D203") (pin "1") (pinfunction "A_1") (pintype "passive"))
      (node (ref "S203") (pin "1") (pinfunction "1_1") (pintype "passive"))
    )
    (net (code "23") (name "Net-(D204-A)") (class "Default")
      (node (ref "D204") (pin "1") (pinfunction "A_1") (pintype "passive"))
      (node (ref "S204") (pin "1") (pinfunction "1_1") (pintype "passive"))
    )
    (net (code "24") (name "Net-(D205-A)") (class "Default")
      (node (ref "D205") (pin "1") (pinfunction "A_1") (pintype "passive"))
      (node (ref "S205") (pin "1") (pinfunction "1_1") (pintype "passive"))
    )
    (net (code "25") (name "Net-(D206-A)") (class "Default")
      (node (ref "D206") (pin "1") (pinfunction "A_1") (pintype "passive"))
      (node (ref "S206") (pin "1") (pinfunction "1_1") (pintype "passive"))
    )
    (net (code "26") (name "Net-(D207-A)") (class "Default")
      (node (ref "D207") (pin "1") (pinfunction "A_1") (pintype "passive"))
      (node (ref "S207") (pin "1") (pinfunction "1_1") (pintype "passive"))
    )
    (net (code "27") (name "Net-(D208-A)") (class "Default")
      (node (ref "D208") (pin "1") (pinfunction "A_1") (pintype "passive"))
      (node (ref "S208") (pin "1") (pinfunction "1_1") (pintype "passive"))
    )
    (net (code "28") (name "Net-(D209-A)") (class "Default")
      (node (ref "D209") (pin "1") (pinfunction "A_1") (pintype "passive"))
      (node (ref "S209") (pin "1") (pinfunction "1_1") (pintype "passive"))
    )
    (net (code "29") (name "Net-(D210-A)") (class "Default")
      (node (ref "D210") (pin "1") (pinfunction "A_1") (pintype "passive"))
      (node (ref "S210") (pin "1") (pinfunction "1_1") (pintype "passive"))
    )
    (net (code "30") (name "Net-(D211-A)") (class "Default")
      (node (ref "D211") (pin "1") (pinfunction "A_1") (pintype "passive"))
      (node (ref "S211") (pin "1") (pinfunction "1_1") (pintype "passive"))
    )
    (net (code "31") (name "Net-(D212-A)") (class "Default")
      (node (ref "D212") (pin "1") (pinfunction "A_1") (pintype "passive"))
      (node (ref "S212") (pin "1") (pinfunction "1_1") (pintype "passive"))
    )
    (net (code "32") (name "Net-(D213-A)") (class "Default")
      (node (ref "D213") (pin "1") (pinfunction "A_1") (pintype "passive"))
      (node (ref "S213") (pin "1") (pinfunction "1_1") (pintype "passive"))
    )
    (net (code "33") (name "Net-(D215-A)") (class "Default")
      (node (ref "D215") (pin "1") (pinfunction "A_1") (pintype "passive"))
      (node (ref "S215") (pin "1") (pinfunction "1_1") (pintype "passive"))
    )
    (net (code "34") (name "Net-(D216-A)") (class "Default")
      (node (ref "D216") (pin "1") (pinfunction "A_1") (pintype "passive"))
      (node (ref "S216") (pin "1") (pinfunction "1_1") (pintype "passive"))
    )
    (net (code "35") (name "Net-(D217-A)") (class "Default")
      (node (ref "D217") (pin "1") (pinfunction "A_1") (pintype "passive"))
      (node (ref "S217") (pin "1") (pinfunction "1_1") (pintype "passive"))
    )
    (net (code "36") (name "Net-(D218-A)") (class "Default")
      (node (ref "D218") (pin "1") (pinfunction "A_1") (pintype "passive"))
      (node (ref "S218") (pin "1") (pinfunction "1_1") (pintype "passive"))
    )
    (net (code "37") (name "Net-(D219-A)") (class "Default")
      (node (ref "D219") (pin "1") (pinfunction "A_1") (pintype "passive"))
      (node (ref "S219") (pin "1") (pinfunction "1_1") (pintype "passive"))
    )
    (net (code "38") (name "Net-(D220-A)") (class "Default")
      (node (ref "D220") (pin "1") (pinfunction "A_1") (pintype "passive"))
      (node (ref "S220") (pin "1") (pinfunction "1_1") (pintype "passive"))
    )
    (net (code "39") (name "Net-(D221-A)") (class "Default")
      (node (ref "D221") (pin "1") (pinfunction "A_1") (pintype "passive"))
      (node (ref "S221") (pin "1") (pinfunction "1_1") (pintype "passive"))
    )
    (net (code "40") (name "Net-(D222-A)") (class "Default")
      (node (ref "D222") (pin "1") (pinfunction "A_1") (pintype "passive"))
      (node (ref "S222") (pin "1") (pinfunction "1_1") (pintype "passive"))
    )
    (net (code "41") (name "Net-(D223-A)") (class "Default")
      (node (ref "D223") (pin "1") (pinfunction "A_1") (pintype "passive"))
      (node (ref "S223") (pin "1") (pinfunction "1_1") (pintype "passive"))
    )
    (net (code "42") (name "Net-(D224-A)") (class "Default")
      (node (ref "D224") (pin "1") (pinfunction "A_1") (pintype "passive"))
      (node (ref "S224") (pin "1") (pinfunction "1_1") (pintype "passive"))
    )
    (net (code "43") (name "Net-(D225-A)") (class "Default")
      (node (ref "D225") (pin "1") (pinfunction "A_1") (pintype "passive"))
      (node (ref "S225") (pin "1") (pinfunction "1_1") (pintype "passive"))
    )
    (net (code "44") (name "Net-(D226-A)") (class "Default")
      (node (ref "D226") (pin "1") (pinfunction "A_1") (pintype "passive"))
      (node (ref "S226") (pin "1") (pinfunction "1_1") (pintype "passive"))
    )
    (net (code "45") (name "Net-(D227-A)") (class "Default")
      (node (ref "D227") (pin "1") (pinfunction "A_1") (pintype "passive"))
      (node (ref "S227") (pin "1") (pinfunction "1_1") (pintype "passive"))
    )
    (net (code "46") (name "Net-(D228-A)") (class "Default")
      (node (ref "D228") (pin "1") (pinfunction "A_1") (pintype "passive"))
      (node (ref "S259") (pin "1") (pinfunction "1_1") (pintype "passive"))
    )
    (net (code "47") (name "Net-(D229-A)") (class "Default")
      (node (ref "D229") (pin "1") (pinfunction "A_1") (pintype "passive"))
      (node (ref "S229") (pin "1") (pinfunction "1_1") (pintype "passive"))
    )
    (net (code "48") (name "Net-(D230-A)") (class "Default")
      (node (ref "D230") (pin "1") (pinfunction "A_1") (pintype "passive"))
      (node (ref "S230") (pin "1") (pinfunction "1_1") (pintype "passive"))
    )
    (net (code "49") (name "Net-(D231-A)") (class "Default")
      (node (ref "D231") (pin "1") (pinfunction "A_1") (pintype "passive"))
      (node (ref "S231") (pin "1") (pinfunction "1_1") (pintype "passive"))
    )
    (net (code "50") (name "Net-(D232-A)") (class "Default")
      (node (ref "D232") (pin "1") (pinfunction "A_1") (pintype "passive"))
      (node (ref "S232") (pin "1") (pinfunction "1_1") (pintype "passive"))
    )
    (net (code "51") (name "Net-(D233-A)") (class "Default")
      (node (ref "D233") (pin "1") (pinfunction "A_1") (pintype "passive"))
      (node (ref "S233") (pin "1") (pinfunction "1_1") (pintype "passive"))
    )
    (net (code "52") (name "Net-(D234-A)") (class "Default")
      (node (ref "D234") (pin "1") (pinfunction "A_1") (pintype "passive"))
      (node (ref "S234") (pin "1") (pinfunction "1_1") (pintype "passive"))
    )
    (net (code "53") (name "Net-(D235-A)") (class "Default")
      (node (ref "D235") (pin "1") (pinfunction "A_1") (pintype "passive"))
      (node (ref "S235") (pin "1") (pinfunction "1_1") (pintype "passive"))
    )
    (net (code "54") (name "Net-(D236-A)") (class "Default")
      (node (ref "D236") (pin "1") (pinfunction "A_1") (pintype "passive"))
      (node (ref "S236") (pin "1") (pinfunction "1_1") (pintype "passive"))
    )
    (net (code "55") (name "Net-(D237-A)") (class "Default")
      (node (ref "D237") (pin "1") (pinfunction "A_1") (pintype "passive"))
      (node (ref "S237") (pin "1") (pinfunction "1_1") (pintype "passive"))
    )
    (net (code "56") (name "Net-(D238-A)") (class "Default")
      (node (ref "D238") (pin "1") (pinfunction "A_1") (pintype "passive"))
      (node (ref "S238") (pin "1") (pinfunction "1_1") (pintype "passive"))
    )
    (net (code "57") (name "Net-(D239-A)") (class "Default")
      (node (ref "D239") (pin "1") (pinfunction "A_1") (pintype "passive"))
      (node (ref "S239") (pin "1") (pinfunction "1_1") (pintype "passive"))
    )
    (net (code "58") (name "Net-(D240-A)") (class "Default")
      (node (ref "D240") (pin "1") (pinfunction "A_1") (pintype "passive"))
      (node (ref "S240") (pin "1") (pinfunction "1_1") (pintype "passive"))
    )
    (net (code "59") (name "Net-(D241-A)") (class "Default")
      (node (ref "D241") (pin "1") (pinfunction "A_1") (pintype "passive"))
      (node (ref "S242") (pin "1") (pinfunction "1_1") (pintype "passive"))
    )
    (net (code "60") (name "Net-(D242-A)") (class "Default")
      (node (ref "D242") (pin "1") (pinfunction "A_1") (pintype "passive"))
      (node (ref "S228") (pin "1") (pinfunction "1_1") (pintype "passive"))
    )
    (net (code "61") (name "Net-(D243-A)") (class "Default")
      (node (ref "D243") (pin "1") (pinfunction "A_1") (pintype "passive"))
      (node (ref "S243") (pin "1") (pinfunction "1_1") (pintype "passive"))
    )
    (net (code "62") (name "Net-(D244-A)") (class "Default")
      (node (ref "D244") (pin "1") (pinfunction "A_1") (pintype "passive"))
      (node (ref "S244") (pin "2") (pinfunction "2_2") (pintype "passive"))
    )
    (net (code "63") (name "Net-(D245-A)") (class "Default")
      (node (ref "D245") (pin "1") (pinfunction "A_1") (pintype "passive"))
      (node (ref "S245") (pin "1") (pinfunction "1_1") (pintype "passive"))
    )
    (net (code "64") (name "Net-(D246-A)") (class "Default")
      (node (ref "D246") (pin "1") (pinfunction "A_1") (pintype "passive"))
      (node (ref "S246") (pin "1") (pinfunction "1_1") (pintype "passive"))
    )
    (net (code "65") (name "Net-(D247-A)") (class "Default")
      (node (ref "D247") (pin "1") (pinfunction "A_1") (pintype "passive"))
      (node (ref "S247") (pin "1") (pinfunction "1_1") (pintype "passive"))
    )
    (net (code "66") (name "Net-(D248-A)") (class "Default")
      (node (ref "D248") (pin "1") (pinfunction "A_1") (pintype "passive"))
      (node (ref "S248") (pin "1") (pinfunction "1_1") (pintype "passive"))
    )
    (net (code "67") (name "Net-(D249-A)") (class "Default")
      (node (ref "D249") (pin "1") (pinfunction "A_1") (pintype "passive"))
      (node (ref "S249") (pin "1") (pinfunction "1_1") (pintype "passive"))
    )
    (net (code "68") (name "Net-(D250-A)") (class "Default")
      (node (ref "D250") (pin "1") (pinfunction "A_1") (pintype "passive"))
      (node (ref "S250") (pin "1") (pinfunction "1_1") (pintype "passive"))
    )
    (net (code "69") (name "Net-(D251-A)") (class "Default")
      (node (ref "D251") (pin "1") (pinfunction "A_1") (pintype "passive"))
      (node (ref "S251") (pin "1") (pinfunction "1_1") (pintype "passive"))
    )
    (net (code "70") (name "Net-(D252-A)") (class "Default")
      (node (ref "D252") (pin "1") (pinfunction "A_1") (pintype "passive"))
      (node (ref "S252") (pin "1") (pinfunction "1_1") (pintype "passive"))
    )
    (net (code "71") (name "Net-(D253-A)") (class "Default")
      (node (ref "D253") (pin "1") (pinfunction "A_1") (pintype "passive"))
      (node (ref "S253") (pin "1") (pinfunction "1_1") (pintype "passive"))
    )
    (net (code "72") (name "Net-(D254-A)") (class "Default")
      (node (ref "D254") (pin "1") (pinfunction "A_1") (pintype "passive"))
      (node (ref "S254") (pin "1") (pinfunction "1_1") (pintype "passive"))
    )
    (net (code "73") (name "Net-(D255-A)") (class "Default")
      (node (ref "D255") (pin "1") (pinfunction "A_1") (pintype "passive"))
      (node (ref "S256") (pin "1") (pinfunction "1_1") (pintype "passive"))
    )
    (net (code "74") (name "Net-(D256-A)") (class "Default")
      (node (ref "D256") (pin "1") (pinfunction "A_1") (pintype "passive"))
      (node (ref "S269") (pin "1") (pinfunction "1_1") (pintype "passive"))
    )
    (net (code "75") (name "Net-(D257-A)") (class "Default")
      (node (ref "D257") (pin "1") (pinfunction "A_1") (pintype "passive"))
      (node (ref "S257") (pin "2") (pinfunction "2_2") (pintype "passive"))
    )
    (net (code "76") (name "Net-(D258-A)") (class "Default")
      (node (ref "D258") (pin "1") (pinfunction "A_1") (pintype "passive"))
      (node (ref "S258") (pin "1") (pinfunction "1_1") (pintype "passive"))
    )
    (net (code "77") (name "Net-(D260-A)") (class "Default")
      (node (ref "D260") (pin "1") (pinfunction "A_1") (pintype "passive"))
      (node (ref "S260") (pin "1") (pinfunction "1_1") (pintype "passive"))
    )
    (net (code "78") (name "Net-(D261-A)") (class "Default")
      (node (ref "D261") (pin "1") (pinfunction "A_1") (pintype "passive"))
      (node (ref "S261") (pin "1") (pinfunction "1_1") (pintype "passive"))
    )
    (net (code "79") (name "Net-(D262-A)") (class "Default")
      (node (ref "D262") (pin "1") (pinfunction "A_1") (pintype "passive"))
      (node (ref "S262") (pin "2") (pinfunction "2_2") (pintype "passive"))
    )
    (net (code "80") (name "Net-(D263-A)") (class "Default")
      (node (ref "D263") (pin "1") (pinfunction "A_1") (pintype "passive"))
      (node (ref "S263") (pin "1") (pinfunction "1_1") (pintype "passive"))
    )
    (net (code "81") (name "Net-(D264-A)") (class "Default")
      (node (ref "D264") (pin "1") (pinfunction "A_1") (pintype "passive"))
      (node (ref "S265") (pin "1") (pinfunction "1_1") (pintype "passive"))
    )
    (net (code "82") (name "Net-(D265-A)") (class "Default")
      (node (ref "D265") (pin "1") (pinfunction "A_1") (pintype "passive"))
      (node (ref "S241") (pin "2") (pinfunction "2_2") (pintype "passive"))
    )
    (net (code "83") (name "Net-(D266-A)") (class "Default")
      (node (ref "D266") (pin "1") (pinfunction "A_1") (pintype "passive"))
      (node (ref "S266") (pin "1") (pinfunction "1_1") (pintype "passive"))
    )
    (net (code "84") (name "unconnected-(STAB1-Pad1)") (class "Default")
      (node (ref "STAB1") (pin "1") (pinfunction "1_1") (pintype "passive"))
    )
    (net (code "85") (name "unconnected-(STAB2-Pad1)") (class "Default")
      (node (ref "STAB2") (pin "1") (pinfunction "1_1") (pintype "passive"))
    )
    (net (code "86") (name "unconnected-(STAB3-Pad1)") (class "Default")
      (node (ref "STAB3") (pin "1") (pinfunction "1_1") (pintype "passive"))
    )
    (net (code "87") (name "unconnected-(STAB4-Pad1)") (class "Default")
      (node (ref "STAB4") (pin "1") (pinfunction "1_1") (pintype "passive"))
    )
    (net (code "88") (name "unconnected-(STAB5-Pad1)") (class "Default")
      (node (ref "STAB5") (pin "1") (pinfunction "1_1") (pintype "passive"))
    )
    (net (code "89") (name "unconnected-(STAB6-Pad1)") (class "Default")
      (node (ref "STAB6") (pin "1") (pinfunction "1_1") (pintype "passive"))
    )
  )
)
